# DisPlay_Switch_Interface.net
KiCad netlist of a schematic drawn in Altium Designer
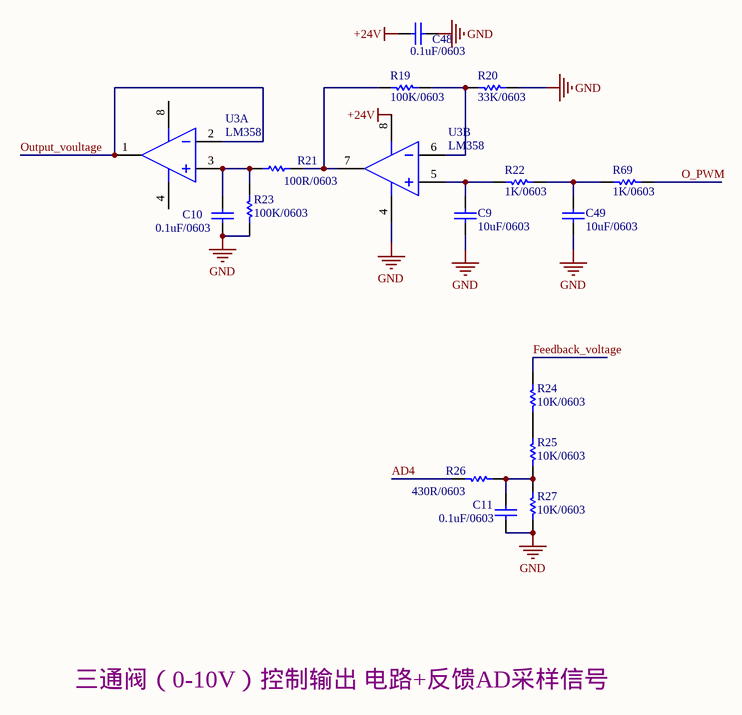
[diagram p0: DisPlay_Switch_Interface.SchDoc]

(export (version "E")
  (design (tool "Eeschema 10.0.6"))
  (components
    (comp (ref "C9")
      (value "10uF/0603")
      (footprint "CAP/SMT/0603C")
      (libsource (lib "Menred_原理图 封装库") (part "CAP/CAP/SMT/0603C"))
    )
    (comp (ref "C10")
      (value "0.1uF/0603")
      (footprint "CAP/SMT/0603C")
      (libsource (lib "Menred_原理图 封装库") (part "CAP/CAP/SMT/0603C"))
    )
    (comp (ref "C11")
      (value "0.1uF/0603")
      (footprint "CAP/SMT/0603C")
      (libsource (lib "Menred_原理图 封装库") (part "CAP/CAP/SMT/0603C"))
    )
    (comp (ref "C48")
      (value "0.1uF/0603")
      (footprint "CAP/SMT/0603C")
      (libsource (lib "") (part "CAP/CAP/SMT/0603C_1"))
    )
    (comp (ref "C49")
      (value "10uF/0603")
      (footprint "CAP/SMT/0603C")
      (libsource (lib "Menred_原理图 封装库") (part "CAP/CAP/SMT/0603C"))
    )
    (comp (ref "R19")
      (value "100K/0603")
      (footprint "0603R")
      (libsource (lib "Menred_原理图 封装库") (part "RES/RES/SMT/0603"))
    )
    (comp (ref "R20")
      (value "33K/0603")
      (footprint "0603R")
      (libsource (lib "Menred_原理图 封装库") (part "RES/RES/SMT/0603"))
    )
    (comp (ref "R21")
      (value "100R/0603")
      (footprint "0603R")
      (libsource (lib "Menred_原理图 封装库") (part "RES/RES/SMT/0603"))
    )
    (comp (ref "R22")
      (value "1K/0603")
      (footprint "0603R")
      (libsource (lib "Menred_原理图 封装库") (part "RES/RES/SMT/0603"))
    )
    (comp (ref "R23")
      (value "100K/0603")
      (footprint "0603R")
      (libsource (lib "") (part "RES/RES/SMT/0603_1"))
    )
    (comp (ref "R24") (value "10K/0603") (footprint "0603R") (libsource (lib "") (part "RES/RES/SMT/0603_1")))
    (comp (ref "R25") (value "10K/0603") (footprint "0603R") (libsource (lib "") (part "RES/RES/SMT/0603_1")))
    (comp (ref "R26")
      (value "430R/0603")
      (footprint "0603R")
      (libsource (lib "Menred_原理图 封装库") (part "RES/RES/SMT/0603"))
    )
    (comp (ref "R27") (value "10K/0603") (footprint "0603R") (libsource (lib "") (part "RES/RES/SMT/0603_1")))
    (comp (ref "R69")
      (value "1K/0603")
      (footprint "0603R")
      (libsource (lib "Menred_原理图 封装库") (part "RES/RES/SMT/0603"))
    )
    (comp (ref "U3")
      (value "LM358")
      (footprint "SOIC-8")
      (description "1MHz 60uA Rail-to-Rail i/o CMOS OP")
      (fields
        (field (name "MANUFACTURER") "ST-Microelectronics")
        (field (name "PUBLISHER") "Altium Hobart Technology Centre")
      )
      (libsource (lib "Menred_原理图 封装库") (part "IC/OP/SMT/SGM358YS/SOIC-8"))
    )
  )
  (nets
    (net (code "1") (name "+24V") (class "Default")
      (node (ref "C48") (pin "2") (pinfunction "2_2") (pintype "passive"))
      (node (ref "U3") (pin "8") (pinfunction "VCC_8") (pintype "power_in"))
    )
    (net (code "2") (name "/AD4") (class "Default")
      (node (ref "R26") (pin "1") (pinfunction "1_1") (pintype "passive"))
    )
    (net (code "3") (name "/Feedback_voltage") (class "Default")
      (node (ref "R24") (pin "2") (pinfunction "2_2") (pintype "passive"))
    )
    (net (code "4") (name "/O_PWM") (class "Default")
      (node (ref "R69") (pin "1") (pinfunction "1_1") (pintype "passive"))
    )
    (net (code "5") (name "/Output_voultage") (class "Default")
      (node (ref "U3") (pin "1") (pinfunction "OUT_1") (pintype "open_collector"))
      (node (ref "U3") (pin "2") (pinfunction "IN-_2") (pintype "passive"))
    )
    (net (code "7") (name "GND") (class "Default")
      (node (ref "C10") (pin "1") (pinfunction "1_1") (pintype "passive"))
      (node (ref "C11") (pin "1") (pinfunction "1_1") (pintype "passive"))
      (node (ref "C48") (pin "1") (pinfunction "1_1") (pintype "passive"))
      (node (ref "C49") (pin "1") (pinfunction "1_1") (pintype "passive"))
      (node (ref "C9") (pin "1") (pinfunction "1_1") (pintype "passive"))
      (node (ref "R20") (pin "1") (pinfunction "1_1") (pintype "passive"))
      (node (ref "R23") (pin "2") (pinfunction "2_2") (pintype "passive"))
      (node (ref "R27") (pin "1") (pinfunction "1_1") (pintype "passive"))
      (node (ref "U3") (pin "4") (pinfunction "GND_4") (pintype "power_in"))
    )
    (net (code "8") (name "Net-(C11-Pad2)") (class "Default")
      (node (ref "C11") (pin "2") (pinfunction "2_2") (pintype "passive"))
      (node (ref "R25") (pin "1") (pinfunction "1_1") (pintype "passive"))
      (node (ref "R26") (pin "2") (pinfunction "2_2") (pintype "passive"))
      (node (ref "R27") (pin "2") (pinfunction "2_2") (pintype "passive"))
    )
    (net (code "9") (name "Net-(C49-Pad2)") (class "Default")
      (node (ref "C49") (pin "2") (pinfunction "2_2") (pintype "passive"))
      (node (ref "R22") (pin "1") (pinfunction "1_1") (pintype "passive"))
      (node (ref "R69") (pin "2") (pinfunction "2_2") (pintype "passive"))
    )
    (net (code "10") (name "Net-(R24-Pad1)") (class "Default")
      (node (ref "R24") (pin "1") (pinfunction "1_1") (pintype "passive"))
      (node (ref "R25") (pin "2") (pinfunction "2_2") (pintype "passive"))
    )
    (net (code "11") (name "Net-(U3A-IN+)") (class "Default")
      (node (ref "C10") (pin "2") (pinfunction "2_2") (pintype "passive"))
      (node (ref "R21") (pin "1") (pinfunction "1_1") (pintype "passive"))
      (node (ref "R23") (pin "1") (pinfunction "1_1") (pintype "passive"))
      (node (ref "U3") (pin "3") (pinfunction "IN+_3") (pintype "passive"))
    )
    (net (code "12") (name "Net-(U3B-IN+)") (class "Default")
      (node (ref "C9") (pin "2") (pinfunction "2_2") (pintype "passive"))
      (node (ref "R22") (pin "2") (pinfunction "2_2") (pintype "passive"))
      (node (ref "U3") (pin "5") (pinfunction "IN+_5") (pintype "passive"))
    )
    (net (code "13") (name "Net-(U3B-IN-)") (class "Default")
      (node (ref "R19") (pin "1") (pinfunction "1_1") (pintype "passive"))
      (node (ref "R20") (pin "2") (pinfunction "2_2") (pintype "passive"))
      (node (ref "U3") (pin "6") (pinfunction "IN-_6") (pintype "passive"))
    )
    (net (code "14") (name "Net-(U3B-OUT)") (class "Default")
      (node (ref "R19") (pin "2") (pinfunction "2_2") (pintype "passive"))
      (node (ref "R21") (pin "2") (pinfunction "2_2") (pintype "passive"))
      (node (ref "U3") (pin "7") (pinfunction "OUT_7") (pintype "open_collector"))
    )
    (net (code "15") (name "unconnected-(U3A-GND-Pad4)") (class "Default")
      (node (ref "U3") (pin "4") (pinfunction "GND_4") (pintype "passive"))
    )
    (net (code "16") (name "unconnected-(U3A-VCC-Pad8)") (class "Default")
      (node (ref "U3") (pin "8") (pinfunction "VCC_8") (pintype "passive"))
    )
  )
)
